# Quad_FC_power_V10_1.net
KiCad netlist of a schematic drawn in Altium Designer
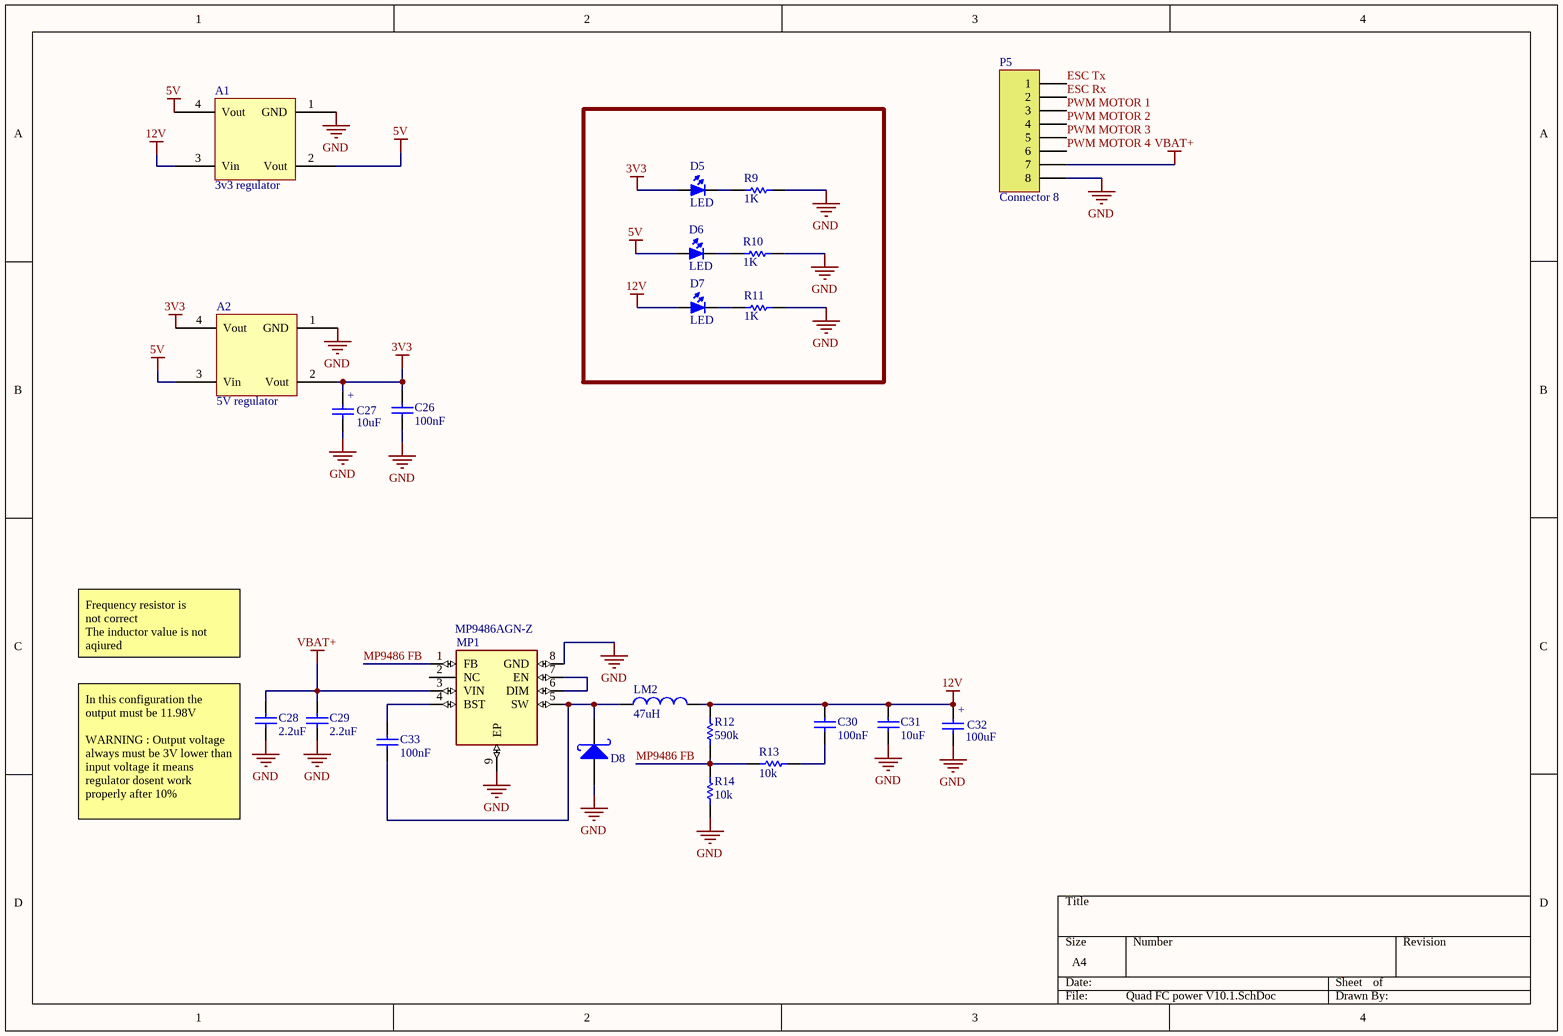
[diagram p0: Quad FC power V10.1.SchDoc]

(export (version "E")
  (design (tool "Eeschema 10.0.6"))
  (components
    (comp (ref "A1")
      (value "3v3 regulator")
      (footprint "SOT230P700X180-4N")
      (libsource (lib "Integrated_Library1") (part "ams1117"))
    )
    (comp (ref "A2")
      (value "5V regulator")
      (footprint "SOT230P700X180-4N")
      (libsource (lib "Integrated_Library1") (part "ams1117"))
    )
    (comp (ref "C26")
      (value "100nF")
      (footprint "CAP0603")
      (description "F407VET6 Power CAP")
      (fields (field (name "DESIGNER") "Abbas Basereh"))
      (libsource (lib "2017AbbasBasereh9365731239 -ver1") (part "CAP SMD PACKAGE"))
    )
    (comp (ref "C27")
      (value "10uF")
      (footprint "MY_CAP_SMD-B")
      (description "3.5X2.8MM")
      (libsource (lib "AMINLIB") (part "CAP_TANTAL_B"))
    )
    (comp (ref "C28")
      (value "2.2uF")
      (footprint "CAPC3413X12N")
      (description "CAP 0805")
      (fields (field (name "DESIGNER") "Abbas Basereh"))
      (libsource (lib "2017AbbasBasereh9365731239 -ver1") (part "CAP SMD 0805"))
    )
    (comp (ref "C29")
      (value "2.2uF")
      (footprint "CAPC3413X12N")
      (description "CAP 0805")
      (fields (field (name "DESIGNER") "Abbas Basereh"))
      (libsource (lib "2017AbbasBasereh9365731239 -ver1") (part "CAP SMD 0805"))
    )
    (comp (ref "C30")
      (value "100nF")
      (footprint "CAP0603")
      (description "F407VET6 Power CAP")
      (fields (field (name "DESIGNER") "Abbas Basereh"))
      (libsource (lib "2017AbbasBasereh9365731239 -ver1") (part "CAP SMD PACKAGE"))
    )
    (comp (ref "C31")
      (value "10uF")
      (footprint "CAPC3413X12N")
      (description "CAP 0805")
      (fields (field (name "DESIGNER") "Abbas Basereh"))
      (libsource (lib "2017AbbasBasereh9365731239 -ver1") (part "CAP SMD 0805"))
    )
    (comp (ref "C32")
      (value "100uF")
      (footprint "MY_CAP_SMD-B")
      (description "3.5X2.8MM")
      (libsource (lib "AMINLIB") (part "CAP_TANTAL_B"))
    )
    (comp (ref "C33")
      (value "100nF")
      (footprint "CAP0603")
      (description "F407VET6 Power CAP")
      (fields (field (name "DESIGNER") "Abbas Basereh"))
      (libsource (lib "2017AbbasBasereh9365731239 -ver1") (part "CAP SMD PACKAGE"))
    )
    (comp (ref "D5")
      (value "LED")
      (footprint "0603 - LED")
      (description "Led")
      (fields (field (name "PUBLISHER") "Altium Limited"))
      (libsource (lib "Sajad_Altium_Library") (part "LED"))
    )
    (comp (ref "D6")
      (value "LED")
      (footprint "0603 - LED")
      (description "Led")
      (fields (field (name "PUBLISHER") "Altium Limited"))
      (libsource (lib "Sajad_Altium_Library") (part "LED"))
    )
    (comp (ref "D7")
      (value "LED")
      (footprint "0603 - LED")
      (description "Led")
      (fields (field (name "PUBLISHER") "Altium Limited"))
      (libsource (lib "Sajad_Altium_Library") (part "LED"))
    )
    (comp (ref "D8")
      (value "SS34")
      (footprint "SS34:DIOM4226X244N")
      (fields
        (field (name "MANUFACTURER") "ON Semiconductor/Fairchild")
        (field (name "DESIGNER") "Abbas Basereh")
      )
      (libsource (lib "2017AbbasBasereh9365731239 -ver1") (part "1n5822 SMD"))
    )
    (comp (ref "LM2")
      (value "47uH")
      (footprint "RLS-105:IND_RLS-105")
      (description "Inductor")
      (fields (field (name "PUBLISHER") "Altium Limited"))
      (libsource (lib "2017AbbasBasereh9365731239 -ver1") (part "L SMA 0.25W"))
    )
    (comp (ref "MP1")
      (value "MP9486AGN-Z")
      (footprint "SOIC127P600X170-9N")
      (description "Buck Switching Regulator IC Positive Fixed 5V 1 Output 1A 8-SOIC (0.154, 3.90mm Width) Exposed Pad")
      (fields (field (name "MF") "Monolithic Power"))
      (libsource (lib "MP9486AGN-Z") (part "MP9486AGN-Z"))
    )
    (comp (ref "P5")
      (value "Connector 8")
      (footprint "JST B8B-PH-K")
      (description "Connector, 8-Pin2.5mm")
      (fields (field (name "PUBLISHER") "Altium Limited"))
      (libsource (lib "Sajad_Altium_Library") (part "Connector1x8"))
    )
    (comp (ref "R9")
      (value "1K")
      (footprint "RES0603")
      (description "TOTAL SMD RESISTOR PACK")
      (fields (field (name "DESIGNER") "Abbas Basereh"))
      (libsource (lib "2017AbbasBasereh9365731239 -ver1") (part "RES SMD PACKAGE"))
    )
    (comp (ref "R10")
      (value "1K")
      (footprint "RES0603")
      (description "TOTAL SMD RESISTOR PACK")
      (fields (field (name "DESIGNER") "Abbas Basereh"))
      (libsource (lib "2017AbbasBasereh9365731239 -ver1") (part "RES SMD PACKAGE"))
    )
    (comp (ref "R11")
      (value "1K")
      (footprint "RES0603")
      (description "TOTAL SMD RESISTOR PACK")
      (fields (field (name "DESIGNER") "Abbas Basereh"))
      (libsource (lib "2017AbbasBasereh9365731239 -ver1") (part "RES SMD PACKAGE"))
    )
    (comp (ref "R12")
      (value "590k")
      (footprint "RES0603")
      (description "To Limit current")
      (fields (field (name "DESIGNER") "Abbas Basereh"))
      (libsource (lib "2017AbbasBasereh9365731239 -ver1") (part "RES SMD PACKAGE"))
    )
    (comp (ref "R13")
      (value "10k")
      (footprint "RES0603")
      (description "To Limit current")
      (fields (field (name "DESIGNER") "Abbas Basereh"))
      (libsource (lib "2017AbbasBasereh9365731239 -ver1") (part "RES SMD PACKAGE"))
    )
    (comp (ref "R14")
      (value "10k")
      (footprint "RES0603")
      (description "To Limit current")
      (fields (field (name "DESIGNER") "Abbas Basereh"))
      (libsource (lib "2017AbbasBasereh9365731239 -ver1") (part "RES SMD PACKAGE"))
    )
  )
  (nets
    (net (code "1") (name "/ESC Rx") (class "Default")
      (node (ref "P5") (pin "2") (pinfunction "2_2") (pintype "passive"))
    )
    (net (code "2") (name "/ESC Tx") (class "Default")
      (node (ref "P5") (pin "1") (pinfunction "1_1") (pintype "passive"))
    )
    (net (code "3") (name "/MP9486 FB") (class "Default")
      (node (ref "MP1") (pin "1") (pinfunction "FB_1") (pintype "bidirectional"))
      (node (ref "R12") (pin "1") (pinfunction "1_1") (pintype "passive"))
      (node (ref "R13") (pin "2") (pinfunction "2_2") (pintype "passive"))
      (node (ref "R14") (pin "2") (pinfunction "2_2") (pintype "passive"))
    )
    (net (code "4") (name "/PWM MOTOR 1") (class "Default")
      (node (ref "P5") (pin "3") (pinfunction "3_3") (pintype "passive"))
    )
    (net (code "5") (name "/PWM MOTOR 2") (class "Default")
      (node (ref "P5") (pin "4") (pinfunction "4_4") (pintype "passive"))
    )
    (net (code "6") (name "/PWM MOTOR 3") (class "Default")
      (node (ref "P5") (pin "5") (pinfunction "5_5") (pintype "passive"))
    )
    (net (code "7") (name "/PWM MOTOR 4") (class "Default")
      (node (ref "P5") (pin "6") (pinfunction "6_6") (pintype "passive"))
    )
    (net (code "8") (name "3V3") (class "Default")
      (node (ref "A2") (pin "2") (pinfunction "Vout_2") (pintype "passive"))
      (node (ref "A2") (pin "4") (pinfunction "Vout_4") (pintype "passive"))
      (node (ref "C26") (pin "2") (pinfunction "2_2") (pintype "passive"))
      (node (ref "C27") (pin "+") (pinfunction "+_+") (pintype "passive"))
      (node (ref "D5") (pin "1") (pinfunction "A_1") (pintype "passive"))
    )
    (net (code "9") (name "5V") (class "Default")
      (node (ref "A1") (pin "2") (pinfunction "Vout_2") (pintype "passive"))
      (node (ref "A1") (pin "4") (pinfunction "Vout_4") (pintype "passive"))
      (node (ref "A2") (pin "3") (pinfunction "Vin_3") (pintype "passive"))
      (node (ref "D6") (pin "1") (pinfunction "A_1") (pintype "passive"))
    )
    (net (code "10") (name "12V") (class "Default")
      (node (ref "A1") (pin "3") (pinfunction "Vin_3") (pintype "passive"))
      (node (ref "C30") (pin "2") (pinfunction "2_2") (pintype "passive"))
      (node (ref "C31") (pin "2") (pinfunction "2_2") (pintype "passive"))
      (node (ref "C32") (pin "+") (pinfunction "+_+") (pintype "passive"))
      (node (ref "D7") (pin "1") (pinfunction "A_1") (pintype "passive"))
      (node (ref "LM2") (pin "2") (pinfunction "2_2") (pintype "passive"))
      (node (ref "R12") (pin "2") (pinfunction "2_2") (pintype "passive"))
    )
    (net (code "11") (name "GND") (class "Default")
      (node (ref "A1") (pin "1") (pinfunction "GND_1") (pintype "passive"))
      (node (ref "A2") (pin "1") (pinfunction "GND_1") (pintype "passive"))
      (node (ref "C26") (pin "1") (pinfunction "1_1") (pintype "passive"))
      (node (ref "C27") (pin "-") (pinfunction "-_-") (pintype "passive"))
      (node (ref "C28") (pin "2") (pinfunction "2_2") (pintype "passive"))
      (node (ref "C29") (pin "2") (pinfunction "2_2") (pintype "passive"))
      (node (ref "C31") (pin "1") (pinfunction "1_1") (pintype "passive"))
      (node (ref "C32") (pin "-") (pinfunction "-_-") (pintype "passive"))
      (node (ref "D8") (pin "1") (pinfunction "A_1") (pintype "passive"))
      (node (ref "MP1") (pin "8") (pinfunction "GND_8") (pintype "bidirectional"))
      (node (ref "MP1") (pin "9") (pinfunction "EP_9") (pintype "bidirectional"))
      (node (ref "P5") (pin "8") (pinfunction "8_8") (pintype "passive"))
      (node (ref "R10") (pin "2") (pinfunction "2_2") (pintype "passive"))
      (node (ref "R11") (pin "2") (pinfunction "2_2") (pintype "passive"))
      (node (ref "R14") (pin "1") (pinfunction "1_1") (pintype "passive"))
      (node (ref "R9") (pin "2") (pinfunction "2_2") (pintype "passive"))
    )
    (net (code "12") (name "Net-(C30-Pad1)") (class "Default")
      (node (ref "C30") (pin "1") (pinfunction "1_1") (pintype "passive"))
      (node (ref "R13") (pin "1") (pinfunction "1_1") (pintype "passive"))
    )
    (net (code "13") (name "Net-(D5-K)") (class "Default")
      (node (ref "D5") (pin "2") (pinfunction "K_2") (pintype "passive"))
      (node (ref "R9") (pin "1") (pinfunction "1_1") (pintype "passive"))
    )
    (net (code "14") (name "Net-(D6-K)") (class "Default")
      (node (ref "D6") (pin "2") (pinfunction "K_2") (pintype "passive"))
      (node (ref "R10") (pin "1") (pinfunction "1_1") (pintype "passive"))
    )
    (net (code "15") (name "Net-(D7-K)") (class "Default")
      (node (ref "D7") (pin "2") (pinfunction "K_2") (pintype "passive"))
      (node (ref "R11") (pin "1") (pinfunction "1_1") (pintype "passive"))
    )
    (net (code "16") (name "Net-(D8-K)") (class "Default")
      (node (ref "C33") (pin "1") (pinfunction "1_1") (pintype "passive"))
      (node (ref "D8") (pin "2") (pinfunction "K_2") (pintype "passive"))
      (node (ref "LM2") (pin "1") (pinfunction "1_1") (pintype "passive"))
      (node (ref "MP1") (pin "5") (pinfunction "SW_5") (pintype "bidirectional"))
    )
    (net (code "17") (name "Net-(MP1-BST)") (class "Default")
      (node (ref "C33") (pin "2") (pinfunction "2_2") (pintype "passive"))
      (node (ref "MP1") (pin "4") (pinfunction "BST_4") (pintype "bidirectional"))
    )
    (net (code "18") (name "Net-(MP1-DIM)") (class "Default")
      (node (ref "MP1") (pin "6") (pinfunction "DIM_6") (pintype "bidirectional"))
      (node (ref "MP1") (pin "7") (pinfunction "EN_7") (pintype "bidirectional"))
    )
    (net (code "19") (name "VBAT+") (class "Default")
      (node (ref "C28") (pin "1") (pinfunction "1_1") (pintype "passive"))
      (node (ref "C29") (pin "1") (pinfunction "1_1") (pintype "passive"))
      (node (ref "MP1") (pin "3") (pinfunction "VIN_3") (pintype "bidirectional"))
      (node (ref "P5") (pin "7") (pinfunction "7_7") (pintype "passive"))
    )
    (net (code "20") (name "unconnected-(MP1-NC-Pad2)") (class "Default")
      (node (ref "MP1") (pin "2") (pinfunction "NC_2") (pintype "passive"))
    )
  )
)
